# Sheet2.net
KiCad netlist of a schematic drawn in Altium Designer
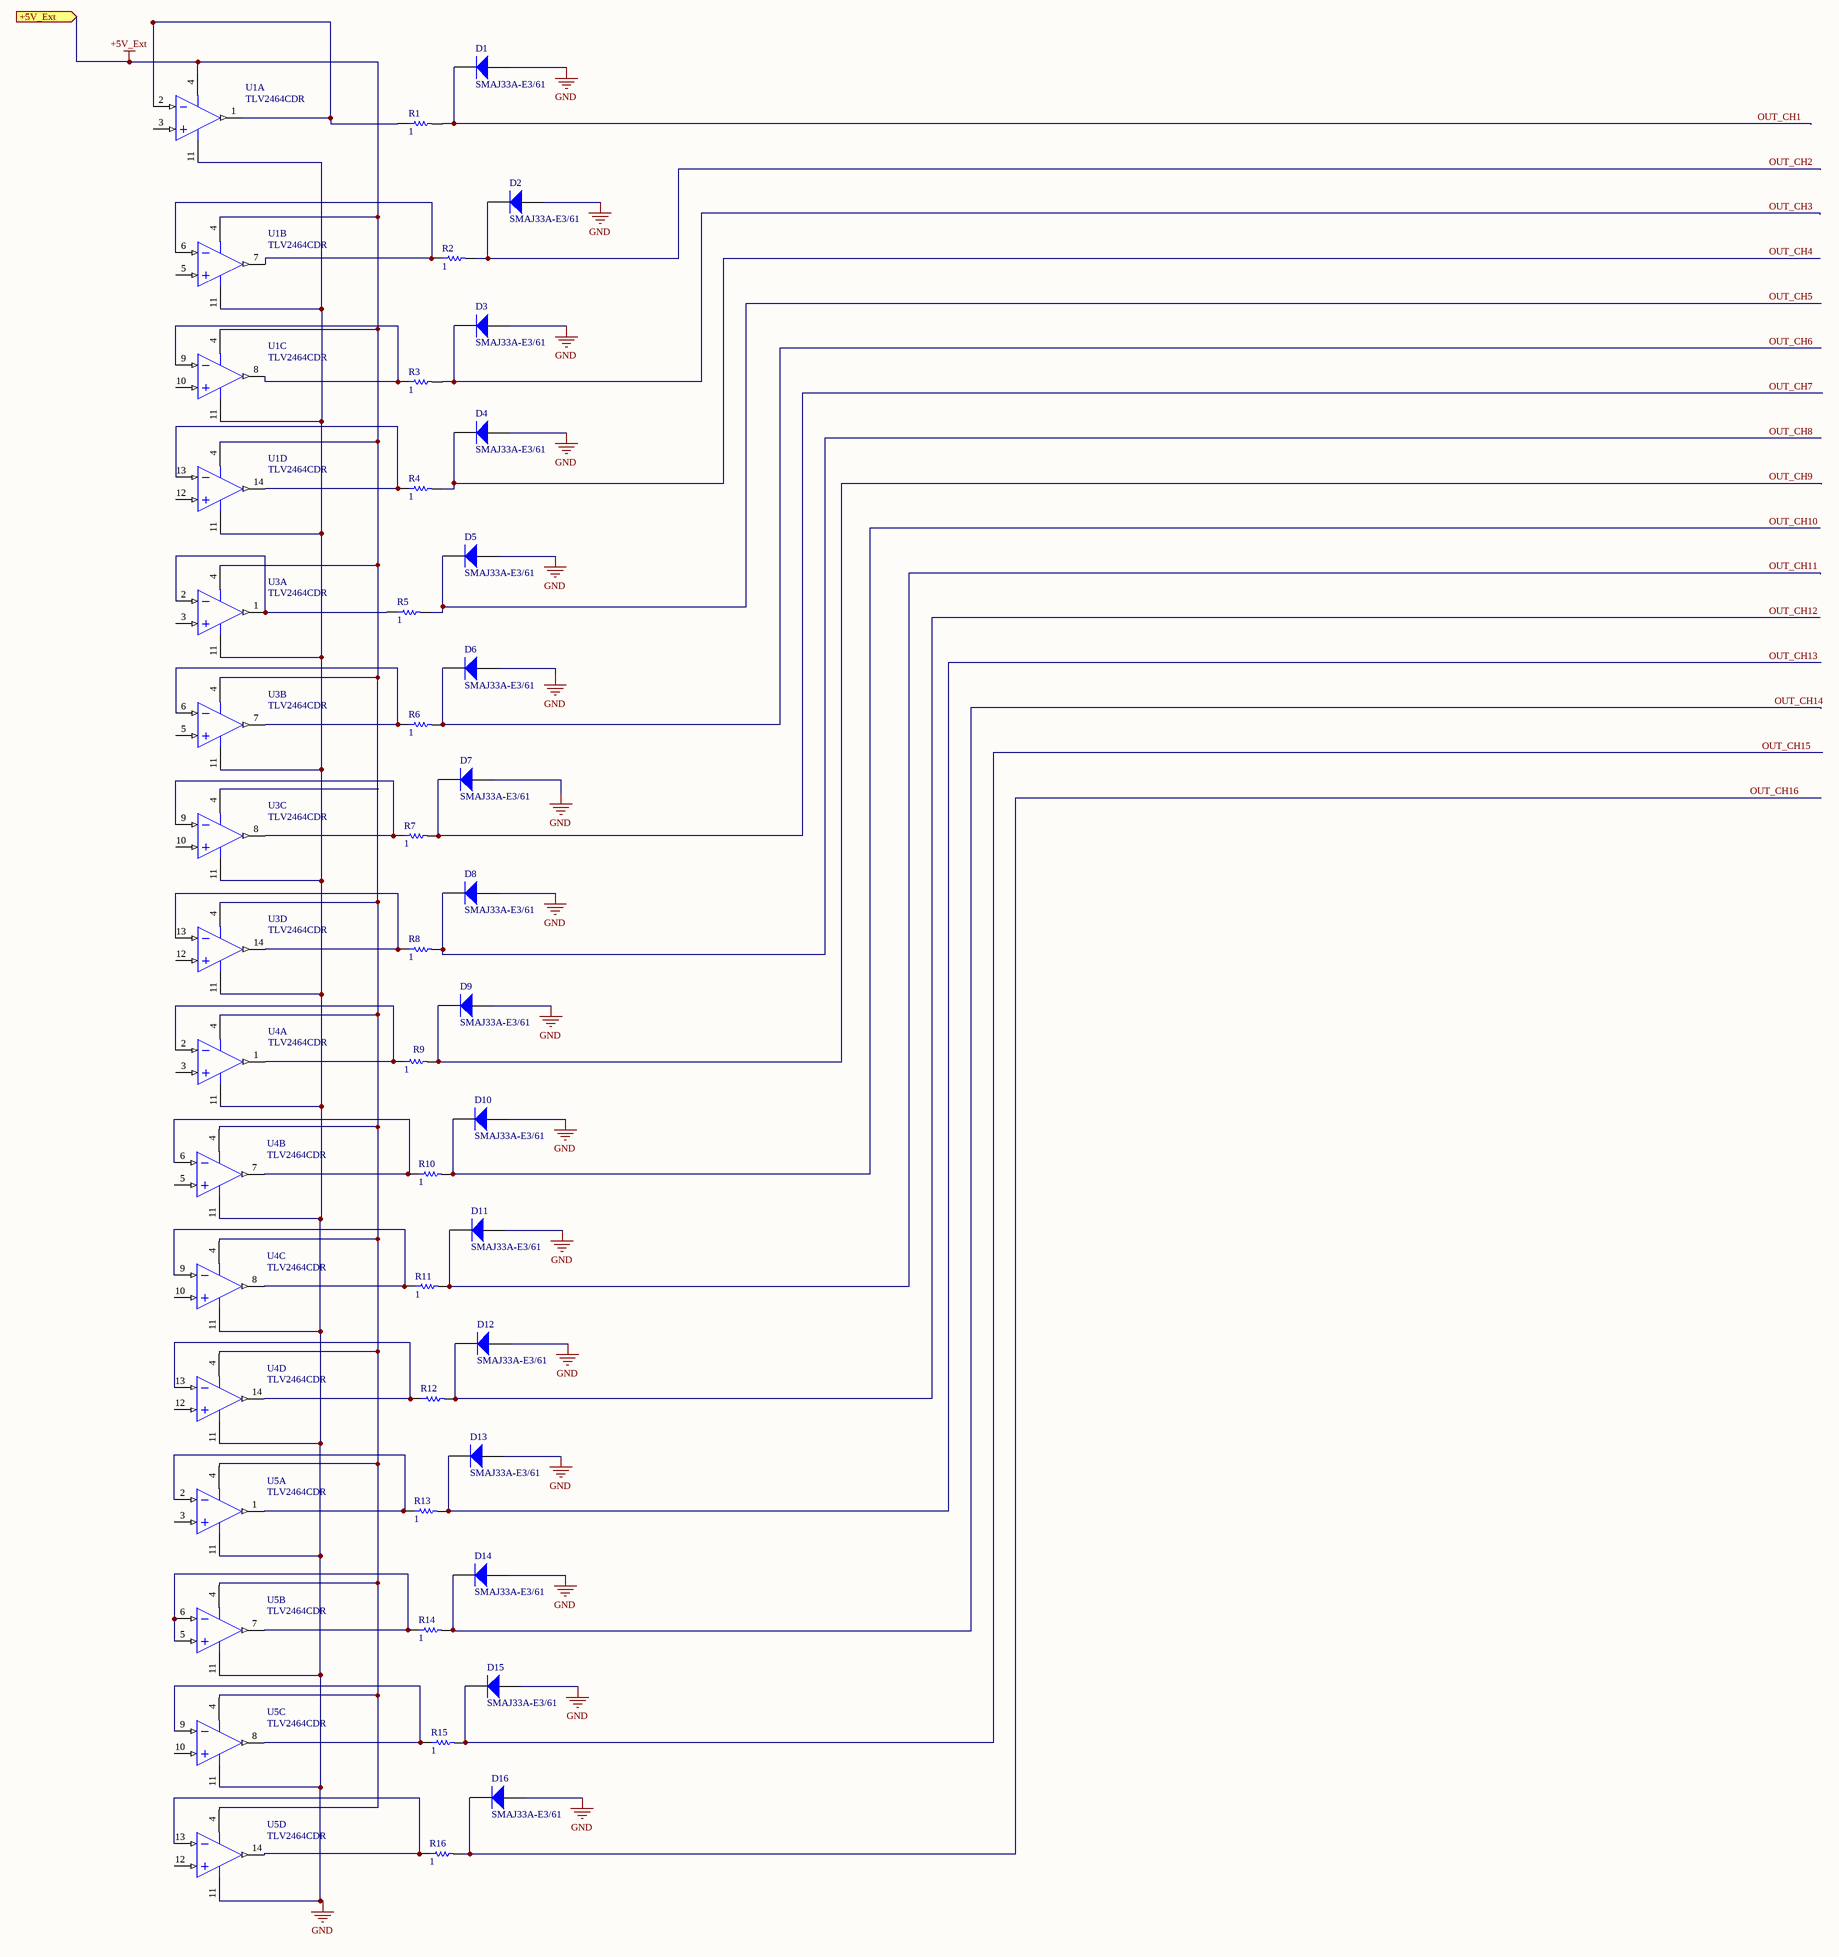
[diagram p0: Sheet2.SchDoc]

(export (version "E")
  (design (tool "Eeschema 10.0.6"))
  (components
    (comp (ref "D1")
      (value "SMAJ33A-E3/61")
      (footprint "VISH-DO-214AC-2_L")
      (fields (field (name "MANUFACTURER") "Vishay Semiconductor"))
      (libsource (lib "Altium Content Vault") (part "VISH-K1A2-2"))
    )
    (comp (ref "D2")
      (value "SMAJ33A-E3/61")
      (footprint "VISH-DO-214AC-2_L")
      (fields (field (name "MANUFACTURER") "Vishay Semiconductor"))
      (libsource (lib "Altium Content Vault") (part "VISH-K1A2-2"))
    )
    (comp (ref "D3")
      (value "SMAJ33A-E3/61")
      (footprint "VISH-DO-214AC-2_L")
      (fields (field (name "MANUFACTURER") "Vishay Semiconductor"))
      (libsource (lib "Altium Content Vault") (part "VISH-K1A2-2"))
    )
    (comp (ref "D4")
      (value "SMAJ33A-E3/61")
      (footprint "VISH-DO-214AC-2_L")
      (fields (field (name "MANUFACTURER") "Vishay Semiconductor"))
      (libsource (lib "Altium Content Vault") (part "VISH-K1A2-2"))
    )
    (comp (ref "D5")
      (value "SMAJ33A-E3/61")
      (footprint "VISH-DO-214AC-2_L")
      (fields (field (name "MANUFACTURER") "Vishay Semiconductor"))
      (libsource (lib "Altium Content Vault") (part "VISH-K1A2-2"))
    )
    (comp (ref "D6")
      (value "SMAJ33A-E3/61")
      (footprint "VISH-DO-214AC-2_L")
      (fields (field (name "MANUFACTURER") "Vishay Semiconductor"))
      (libsource (lib "Altium Content Vault") (part "VISH-K1A2-2"))
    )
    (comp (ref "D7")
      (value "SMAJ33A-E3/61")
      (footprint "VISH-DO-214AC-2_L")
      (fields (field (name "MANUFACTURER") "Vishay Semiconductor"))
      (libsource (lib "Altium Content Vault") (part "VISH-K1A2-2"))
    )
    (comp (ref "D8")
      (value "SMAJ33A-E3/61")
      (footprint "VISH-DO-214AC-2_L")
      (fields (field (name "MANUFACTURER") "Vishay Semiconductor"))
      (libsource (lib "Altium Content Vault") (part "VISH-K1A2-2"))
    )
    (comp (ref "D9")
      (value "SMAJ33A-E3/61")
      (footprint "VISH-DO-214AC-2_L")
      (fields (field (name "MANUFACTURER") "Vishay Semiconductor"))
      (libsource (lib "Altium Content Vault") (part "VISH-K1A2-2"))
    )
    (comp (ref "D10")
      (value "SMAJ33A-E3/61")
      (footprint "VISH-DO-214AC-2_L")
      (fields (field (name "MANUFACTURER") "Vishay Semiconductor"))
      (libsource (lib "Altium Content Vault") (part "VISH-K1A2-2"))
    )
    (comp (ref "D11")
      (value "SMAJ33A-E3/61")
      (footprint "VISH-DO-214AC-2_L")
      (fields (field (name "MANUFACTURER") "Vishay Semiconductor"))
      (libsource (lib "Altium Content Vault") (part "VISH-K1A2-2"))
    )
    (comp (ref "D12")
      (value "SMAJ33A-E3/61")
      (footprint "VISH-DO-214AC-2_L")
      (fields (field (name "MANUFACTURER") "Vishay Semiconductor"))
      (libsource (lib "Altium Content Vault") (part "VISH-K1A2-2"))
    )
    (comp (ref "D13")
      (value "SMAJ33A-E3/61")
      (footprint "VISH-DO-214AC-2_L")
      (fields (field (name "MANUFACTURER") "Vishay Semiconductor"))
      (libsource (lib "Altium Content Vault") (part "VISH-K1A2-2"))
    )
    (comp (ref "D14")
      (value "SMAJ33A-E3/61")
      (footprint "VISH-DO-214AC-2_L")
      (fields (field (name "MANUFACTURER") "Vishay Semiconductor"))
      (libsource (lib "Altium Content Vault") (part "VISH-K1A2-2"))
    )
    (comp (ref "D15")
      (value "SMAJ33A-E3/61")
      (footprint "VISH-DO-214AC-2_L")
      (fields (field (name "MANUFACTURER") "Vishay Semiconductor"))
      (libsource (lib "Altium Content Vault") (part "VISH-K1A2-2"))
    )
    (comp (ref "D16")
      (value "SMAJ33A-E3/61")
      (footprint "VISH-DO-214AC-2_L")
      (fields (field (name "MANUFACTURER") "Vishay Semiconductor"))
      (libsource (lib "Altium Content Vault") (part "VISH-K1A2-2"))
    )
    (comp (ref "R1")
      (value "1")
      (description "Resistor")
      (libsource (lib "Simulation Generic Components") (part "Resistor"))
    )
    (comp (ref "R2")
      (value "1")
      (description "Resistor")
      (libsource (lib "Simulation Generic Components") (part "Resistor"))
    )
    (comp (ref "R3")
      (value "1")
      (description "Resistor")
      (libsource (lib "Simulation Generic Components") (part "Resistor"))
    )
    (comp (ref "R4")
      (value "1")
      (description "Resistor")
      (libsource (lib "Simulation Generic Components") (part "Resistor"))
    )
    (comp (ref "R5")
      (value "1")
      (description "Resistor")
      (libsource (lib "Simulation Generic Components") (part "Resistor"))
    )
    (comp (ref "R6")
      (value "1")
      (description "Resistor")
      (libsource (lib "Simulation Generic Components") (part "Resistor"))
    )
    (comp (ref "R7")
      (value "1")
      (description "Resistor")
      (libsource (lib "Simulation Generic Components") (part "Resistor"))
    )
    (comp (ref "R8")
      (value "1")
      (description "Resistor")
      (libsource (lib "Simulation Generic Components") (part "Resistor"))
    )
    (comp (ref "R9")
      (value "1")
      (description "Resistor")
      (libsource (lib "Simulation Generic Components") (part "Resistor"))
    )
    (comp (ref "R10")
      (value "1")
      (description "Resistor")
      (libsource (lib "Simulation Generic Components") (part "Resistor"))
    )
    (comp (ref "R11")
      (value "1")
      (description "Resistor")
      (libsource (lib "Simulation Generic Components") (part "Resistor"))
    )
    (comp (ref "R12") (value "Resistor") (libsource (lib "Simulation Generic Components") (part "Resistor")))
    (comp (ref "R13")
      (value "1")
      (description "Resistor")
      (libsource (lib "Simulation Generic Components") (part "Resistor"))
    )
    (comp (ref "R14")
      (value "1")
      (description "Resistor")
      (libsource (lib "Simulation Generic Components") (part "Resistor"))
    )
    (comp (ref "R15")
      (value "1")
      (description "Resistor")
      (libsource (lib "Simulation Generic Components") (part "Resistor"))
    )
    (comp (ref "R16")
      (value "1")
      (description "Resistor")
      (libsource (lib "Simulation Generic Components") (part "Resistor"))
    )
    (comp (ref "U1")
      (value "TLV2464CDR")
      (footprint "D0014A_N")
      (fields (field (name "MANUFACTURER") "Texas Instruments"))
      (libsource (lib "Altium Content Vault") (part "TI-TLV2464X-XX14"))
    )
    (comp (ref "U3")
      (value "TLV2464CDR")
      (footprint "D0014A_N")
      (fields (field (name "MANUFACTURER") "Texas Instruments"))
      (libsource (lib "Altium Content Vault") (part "TI-TLV2464X-XX14"))
    )
    (comp (ref "U4")
      (value "TLV2464CDR")
      (footprint "D0014A_N")
      (fields (field (name "MANUFACTURER") "Texas Instruments"))
      (libsource (lib "Altium Content Vault") (part "TI-TLV2464X-XX14"))
    )
    (comp (ref "U5")
      (value "TLV2464CDR")
      (footprint "D0014A_N")
      (fields (field (name "MANUFACTURER") "Texas Instruments"))
      (libsource (lib "Altium Content Vault") (part "TI-TLV2464X-XX14"))
    )
  )
  (nets
    (net (code "1") (name "+5V_Ext") (class "Default")
      (node (ref "U1") (pin "4") (pinfunction "VDD+_4") (pintype "power_in"))
      (node (ref "U3") (pin "4") (pinfunction "VDD+_4") (pintype "power_in"))
      (node (ref "U4") (pin "4") (pinfunction "VDD+_4") (pintype "power_in"))
      (node (ref "U5") (pin "4") (pinfunction "VDD+_4") (pintype "power_in"))
    )
    (net (code "2") (name "/OUT_CH1") (class "Default")
      (node (ref "D1") (pin "1") (pinfunction "K_1") (pintype "passive"))
      (node (ref "R1") (pin "2") (pinfunction "2_2") (pintype "passive"))
    )
    (net (code "3") (name "/OUT_CH2") (class "Default")
      (node (ref "D2") (pin "1") (pinfunction "K_1") (pintype "passive"))
      (node (ref "R2") (pin "2") (pinfunction "2_2") (pintype "passive"))
    )
    (net (code "4") (name "/OUT_CH3") (class "Default")
      (node (ref "D3") (pin "1") (pinfunction "K_1") (pintype "passive"))
      (node (ref "R3") (pin "2") (pinfunction "2_2") (pintype "passive"))
    )
    (net (code "5") (name "/OUT_CH4") (class "Default")
      (node (ref "D4") (pin "1") (pinfunction "K_1") (pintype "passive"))
      (node (ref "R4") (pin "2") (pinfunction "2_2") (pintype "passive"))
    )
    (net (code "6") (name "/OUT_CH5") (class "Default")
      (node (ref "D5") (pin "1") (pinfunction "K_1") (pintype "passive"))
      (node (ref "R5") (pin "2") (pinfunction "2_2") (pintype "passive"))
    )
    (net (code "7") (name "/OUT_CH6") (class "Default")
      (node (ref "D6") (pin "1") (pinfunction "K_1") (pintype "passive"))
      (node (ref "R6") (pin "2") (pinfunction "2_2") (pintype "passive"))
    )
    (net (code "8") (name "/OUT_CH7") (class "Default")
      (node (ref "D7") (pin "1") (pinfunction "K_1") (pintype "passive"))
      (node (ref "R7") (pin "2") (pinfunction "2_2") (pintype "passive"))
    )
    (net (code "9") (name "/OUT_CH8") (class "Default")
      (node (ref "D8") (pin "1") (pinfunction "K_1") (pintype "passive"))
      (node (ref "R8") (pin "2") (pinfunction "2_2") (pintype "passive"))
    )
    (net (code "10") (name "/OUT_CH9") (class "Default")
      (node (ref "D9") (pin "1") (pinfunction "K_1") (pintype "passive"))
      (node (ref "R9") (pin "2") (pinfunction "2_2") (pintype "passive"))
    )
    (net (code "11") (name "/OUT_CH10") (class "Default")
      (node (ref "D10") (pin "1") (pinfunction "K_1") (pintype "passive"))
      (node (ref "R10") (pin "2") (pinfunction "2_2") (pintype "passive"))
    )
    (net (code "12") (name "/OUT_CH11") (class "Default")
      (node (ref "D11") (pin "1") (pinfunction "K_1") (pintype "passive"))
      (node (ref "R11") (pin "2") (pinfunction "2_2") (pintype "passive"))
    )
    (net (code "13") (name "/OUT_CH12") (class "Default")
      (node (ref "D12") (pin "1") (pinfunction "K_1") (pintype "passive"))
      (node (ref "R12") (pin "2") (pinfunction "2_2") (pintype "passive"))
    )
    (net (code "14") (name "/OUT_CH13") (class "Default")
      (node (ref "D13") (pin "1") (pinfunction "K_1") (pintype "passive"))
      (node (ref "R13") (pin "2") (pinfunction "2_2") (pintype "passive"))
    )
    (net (code "15") (name "/OUT_CH14") (class "Default")
      (node (ref "D14") (pin "1") (pinfunction "K_1") (pintype "passive"))
      (node (ref "R14") (pin "2") (pinfunction "2_2") (pintype "passive"))
    )
    (net (code "16") (name "/OUT_CH15") (class "Default")
      (node (ref "D15") (pin "1") (pinfunction "K_1") (pintype "passive"))
      (node (ref "R15") (pin "2") (pinfunction "2_2") (pintype "passive"))
    )
    (net (code "17") (name "/OUT_CH16") (class "Default")
      (node (ref "D16") (pin "1") (pinfunction "K_1") (pintype "passive"))
      (node (ref "R16") (pin "2") (pinfunction "2_2") (pintype "passive"))
    )
    (net (code "18") (name "GND") (class "Default")
      (node (ref "D1") (pin "2") (pinfunction "A_2") (pintype "passive"))
      (node (ref "D10") (pin "2") (pinfunction "A_2") (pintype "passive"))
      (node (ref "D11") (pin "2") (pinfunction "A_2") (pintype "passive"))
      (node (ref "D12") (pin "2") (pinfunction "A_2") (pintype "passive"))
      (node (ref "D13") (pin "2") (pinfunction "A_2") (pintype "passive"))
      (node (ref "D14") (pin "2") (pinfunction "A_2") (pintype "passive"))
      (node (ref "D15") (pin "2") (pinfunction "A_2") (pintype "passive"))
      (node (ref "D16") (pin "2") (pinfunction "A_2") (pintype "passive"))
      (node (ref "D2") (pin "2") (pinfunction "A_2") (pintype "passive"))
      (node (ref "D3") (pin "2") (pinfunction "A_2") (pintype "passive"))
      (node (ref "D4") (pin "2") (pinfunction "A_2") (pintype "passive"))
      (node (ref "D5") (pin "2") (pinfunction "A_2") (pintype "passive"))
      (node (ref "D6") (pin "2") (pinfunction "A_2") (pintype "passive"))
      (node (ref "D7") (pin "2") (pinfunction "A_2") (pintype "passive"))
      (node (ref "D8") (pin "2") (pinfunction "A_2") (pintype "passive"))
      (node (ref "D9") (pin "2") (pinfunction "A_2") (pintype "passive"))
      (node (ref "U3") (pin "11") (pinfunction "GND_11") (pintype "power_in"))
      (node (ref "U4") (pin "11") (pinfunction "GND_11") (pintype "power_in"))
      (node (ref "U5") (pin "11") (pinfunction "GND_11") (pintype "power_in"))
    )
    (net (code "19") (name "Net-(U1A-GND)") (class "Default")
      (node (ref "U1") (pin "11") (pinfunction "GND_11") (pintype "power_in"))
      (node (ref "U3") (pin "11") (pinfunction "GND_11") (pintype "power_in"))
    )
    (net (code "20") (name "Net-(U1A-IN1-)") (class "Default")
      (node (ref "R1") (pin "1") (pinfunction "1_1") (pintype "passive"))
      (node (ref "U1") (pin "1") (pinfunction "OUT1_1") (pintype "output"))
      (node (ref "U1") (pin "2") (pinfunction "IN1-_2") (pintype "input"))
    )
    (net (code "21") (name "Net-(U1B-IN2-)") (class "Default")
      (node (ref "R2") (pin "1") (pinfunction "1_1") (pintype "passive"))
      (node (ref "U1") (pin "6") (pinfunction "IN2-_6") (pintype "input"))
      (node (ref "U1") (pin "7") (pinfunction "OUT2_7") (pintype "output"))
    )
    (net (code "22") (name "Net-(U1C-IN3-)") (class "Default")
      (node (ref "R3") (pin "1") (pinfunction "1_1") (pintype "passive"))
      (node (ref "U1") (pin "8") (pinfunction "OUT3_8") (pintype "output"))
      (node (ref "U1") (pin "9") (pinfunction "IN3-_9") (pintype "input"))
    )
    (net (code "23") (name "Net-(U1D-IN4-)") (class "Default")
      (node (ref "R4") (pin "1") (pinfunction "1_1") (pintype "passive"))
      (node (ref "U1") (pin "13") (pinfunction "IN4-_13") (pintype "input"))
      (node (ref "U1") (pin "14") (pinfunction "OUT4_14") (pintype "output"))
    )
    (net (code "24") (name "Net-(U3A-IN1-)") (class "Default")
      (node (ref "R5") (pin "1") (pinfunction "1_1") (pintype "passive"))
      (node (ref "U3") (pin "1") (pinfunction "OUT1_1") (pintype "output"))
      (node (ref "U3") (pin "2") (pinfunction "IN1-_2") (pintype "input"))
    )
    (net (code "25") (name "Net-(U3B-IN2-)") (class "Default")
      (node (ref "R6") (pin "1") (pinfunction "1_1") (pintype "passive"))
      (node (ref "U3") (pin "6") (pinfunction "IN2-_6") (pintype "input"))
      (node (ref "U3") (pin "7") (pinfunction "OUT2_7") (pintype "output"))
    )
    (net (code "26") (name "Net-(U3C-IN3-)") (class "Default")
      (node (ref "R7") (pin "1") (pinfunction "1_1") (pintype "passive"))
      (node (ref "U3") (pin "8") (pinfunction "OUT3_8") (pintype "output"))
      (node (ref "U3") (pin "9") (pinfunction "IN3-_9") (pintype "input"))
    )
    (net (code "27") (name "Net-(U3D-IN4-)") (class "Default")
      (node (ref "R8") (pin "1") (pinfunction "1_1") (pintype "passive"))
      (node (ref "U3") (pin "13") (pinfunction "IN4-_13") (pintype "input"))
      (node (ref "U3") (pin "14") (pinfunction "OUT4_14") (pintype "output"))
    )
    (net (code "28") (name "Net-(U4A-IN1-)") (class "Default")
      (node (ref "R9") (pin "1") (pinfunction "1_1") (pintype "passive"))
      (node (ref "U4") (pin "1") (pinfunction "OUT1_1") (pintype "output"))
      (node (ref "U4") (pin "2") (pinfunction "IN1-_2") (pintype "input"))
    )
    (net (code "29") (name "Net-(U4B-IN2-)") (class "Default")
      (node (ref "R10") (pin "1") (pinfunction "1_1") (pintype "passive"))
      (node (ref "U4") (pin "6") (pinfunction "IN2-_6") (pintype "input"))
      (node (ref "U4") (pin "7") (pinfunction "OUT2_7") (pintype "output"))
    )
    (net (code "30") (name "Net-(U4C-IN3-)") (class "Default")
      (node (ref "R11") (pin "1") (pinfunction "1_1") (pintype "passive"))
      (node (ref "U4") (pin "8") (pinfunction "OUT3_8") (pintype "output"))
      (node (ref "U4") (pin "9") (pinfunction "IN3-_9") (pintype "input"))
    )
    (net (code "31") (name "Net-(U4D-IN4-)") (class "Default")
      (node (ref "R12") (pin "1") (pinfunction "1_1") (pintype "passive"))
      (node (ref "U4") (pin "13") (pinfunction "IN4-_13") (pintype "input"))
      (node (ref "U4") (pin "14") (pinfunction "OUT4_14") (pintype "output"))
    )
    (net (code "32") (name "Net-(U5A-IN1-)") (class "Default")
      (node (ref "R13") (pin "1") (pinfunction "1_1") (pintype "passive"))
      (node (ref "U5") (pin "1") (pinfunction "OUT1_1") (pintype "output"))
      (node (ref "U5") (pin "2") (pinfunction "IN1-_2") (pintype "input"))
    )
    (net (code "33") (name "Net-(U5B-IN2+)") (class "Default")
      (node (ref "R14") (pin "1") (pinfunction "1_1") (pintype "passive"))
      (node (ref "U5") (pin "5") (pinfunction "IN2+_5") (pintype "input"))
      (node (ref "U5") (pin "6") (pinfunction "IN2-_6") (pintype "input"))
      (node (ref "U5") (pin "7") (pinfunction "OUT2_7") (pintype "output"))
    )
    (net (code "34") (name "Net-(U5C-IN3-)") (class "Default")
      (node (ref "R15") (pin "1") (pinfunction "1_1") (pintype "passive"))
      (node (ref "U5") (pin "8") (pinfunction "OUT3_8") (pintype "output"))
      (node (ref "U5") (pin "9") (pinfunction "IN3-_9") (pintype "input"))
    )
    (net (code "35") (name "Net-(U5D-IN4-)") (class "Default")
      (node (ref "R16") (pin "1") (pinfunction "1_1") (pintype "passive"))
      (node (ref "U5") (pin "13") (pinfunction "IN4-_13") (pintype "input"))
      (node (ref "U5") (pin "14") (pinfunction "OUT4_14") (pintype "output"))
    )
    (net (code "36") (name "unconnected-(U1A-IN1+-Pad3)") (class "Default")
      (node (ref "U1") (pin "3") (pinfunction "IN1+_3") (pintype "input"))
    )
    (net (code "37") (name "unconnected-(U1B-IN2+-Pad5)") (class "Default")
      (node (ref "U1") (pin "5") (pinfunction "IN2+_5") (pintype "input"))
    )
    (net (code "38") (name "unconnected-(U1C-IN3+-Pad10)") (class "Default")
      (node (ref "U1") (pin "10") (pinfunction "IN3+_10") (pintype "input"))
    )
    (net (code "39") (name "unconnected-(U1D-IN4+-Pad12)") (class "Default")
      (node (ref "U1") (pin "12") (pinfunction "IN4+_12") (pintype "input"))
    )
    (net (code "40") (name "unconnected-(U3A-IN1+-Pad3)") (class "Default")
      (node (ref "U3") (pin "3") (pinfunction "IN1+_3") (pintype "input"))
    )
    (net (code "41") (name "unconnected-(U3B-IN2+-Pad5)") (class "Default")
      (node (ref "U3") (pin "5") (pinfunction "IN2+_5") (pintype "input"))
    )
    (net (code "42") (name "unconnected-(U3C-IN3+-Pad10)") (class "Default")
      (node (ref "U3") (pin "10") (pinfunction "IN3+_10") (pintype "input"))
    )
    (net (code "43") (name "unconnected-(U3C-VDD+-Pad4)") (class "Default")
      (node (ref "U3") (pin "4") (pinfunction "VDD+_4") (pintype "power_in"))
    )
    (net (code "44") (name "unconnected-(U3D-IN4+-Pad12)") (class "Default")
      (node (ref "U3") (pin "12") (pinfunction "IN4+_12") (pintype "input"))
    )
    (net (code "45") (name "unconnected-(U4A-IN1+-Pad3)") (class "Default")
      (node (ref "U4") (pin "3") (pinfunction "IN1+_3") (pintype "input"))
    )
    (net (code "46") (name "unconnected-(U4B-IN2+-Pad5)") (class "Default")
      (node (ref "U4") (pin "5") (pinfunction "IN2+_5") (pintype "input"))
    )
    (net (code "47") (name "unconnected-(U4C-IN3+-Pad10)") (class "Default")
      (node (ref "U4") (pin "10") (pinfunction "IN3+_10") (pintype "input"))
    )
    (net (code "48") (name "unconnected-(U4D-IN4+-Pad12)") (class "Default")
      (node (ref "U4") (pin "12") (pinfunction "IN4+_12") (pintype "input"))
    )
    (net (code "49") (name "unconnected-(U5A-IN1+-Pad3)") (class "Default")
      (node (ref "U5") (pin "3") (pinfunction "IN1+_3") (pintype "input"))
    )
    (net (code "50") (name "unconnected-(U5C-IN3+-Pad10)") (class "Default")
      (node (ref "U5") (pin "10") (pinfunction "IN3+_10") (pintype "input"))
    )
    (net (code "51") (name "unconnected-(U5D-IN4+-Pad12)") (class "Default")
      (node (ref "U5") (pin "12") (pinfunction "IN4+_12") (pintype "input"))
    )
  )
)
